# clock1.net
KiCad netlist of a schematic drawn in EAGLE
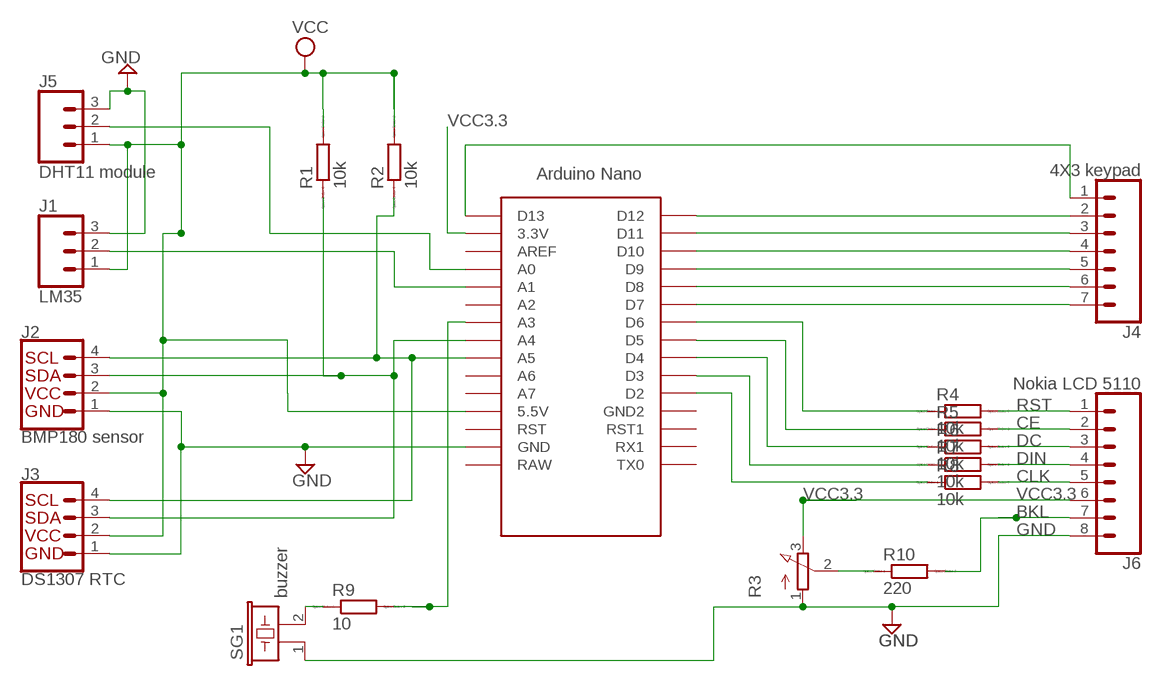
[diagram p0: schematic, sheet 1]

(export (version "E")
  (design (tool "Eeschema 10.0.6"))
  (components
    (comp (ref "J1")
      (value "LM35")
      (footprint "eagle-import:1X03")
      (libsource (lib "eagle-import") (part "CONN_03"))
    )
    (comp (ref "J2")
      (value "BMP180 sensor")
      (footprint "eagle-import:1X04")
      (libsource (lib "eagle-import") (part "I2C_STANDARD"))
    )
    (comp (ref "J3")
      (value "DS1307 RTC")
      (footprint "eagle-import:1X04")
      (libsource (lib "eagle-import") (part "I2C_STANDARD"))
    )
    (comp (ref "J4")
      (value "4X3 keypad")
      (footprint "eagle-import:1X07")
      (libsource (lib "eagle-import") (part "CONN_07"))
    )
    (comp (ref "J5")
      (value "DHT11 module")
      (footprint "eagle-import:1X03")
      (libsource (lib "eagle-import") (part "CONN_03"))
    )
    (comp (ref "J6")
      (value "Nokia LCD 5110")
      (footprint "eagle-import:1X08")
      (libsource (lib "eagle-import") (part "CONN_08{dblquote}"))
    )
    (comp (ref "R1")
      (value "10k")
      (footprint "eagle-import:0204_7")
      (libsource (lib "eagle-import") (part "R0204/7"))
    )
    (comp (ref "R2")
      (value "10k")
      (footprint "eagle-import:0204_7")
      (libsource (lib "eagle-import") (part "R0204/7"))
    )
    (comp (ref "R3")
      (value "3RP/1610N")
      (footprint "eagle-import:3RP_1610N")
      (libsource (lib "eagle-import") (part "3RP/1610N"))
    )
    (comp (ref "R4")
      (value "10k")
      (footprint "eagle-import:0204_7")
      (libsource (lib "eagle-import") (part "R0204/7"))
    )
    (comp (ref "R5")
      (value "10k")
      (footprint "eagle-import:0204_7")
      (libsource (lib "eagle-import") (part "R0204/7"))
    )
    (comp (ref "R6")
      (value "10k")
      (footprint "eagle-import:0204_7")
      (libsource (lib "eagle-import") (part "R0204/7"))
    )
    (comp (ref "R7")
      (value "10k")
      (footprint "eagle-import:0204_7")
      (libsource (lib "eagle-import") (part "R0204/7"))
    )
    (comp (ref "R8")
      (value "10k")
      (footprint "eagle-import:0204_7")
      (libsource (lib "eagle-import") (part "R0204/7"))
    )
    (comp (ref "R9")
      (value "10")
      (footprint "eagle-import:0204_7")
      (libsource (lib "eagle-import") (part "R0204/7"))
    )
    (comp (ref "R10")
      (value "220")
      (footprint "eagle-import:0204_7")
      (libsource (lib "eagle-import") (part "R0204/7"))
    )
    (comp (ref "SG1")
      (value "buzzer")
      (footprint "eagle-import:B_C11L")
      (libsource (lib "eagle-import") (part "B/C11L"))
    )
    (comp (ref "U$1")
      (value "NANO")
      (footprint "eagle-import:NANO")
      (libsource (lib "eagle-import") (part "NANO"))
    )
  )
  (nets
    (net (code "1") (name "/BKL") (class "Default")
      (node (ref "J6") (pin "7") (pinfunction "7_7") (pintype "passive"))
      (node (ref "R10") (pin "2") (pinfunction "2_2") (pintype "passive"))
    )
    (net (code "2") (name "/CE") (class "Default")
      (node (ref "J6") (pin "2") (pinfunction "2_2") (pintype "passive"))
      (node (ref "R5") (pin "2") (pinfunction "2_2") (pintype "passive"))
    )
    (net (code "3") (name "/CLK") (class "Default")
      (node (ref "J6") (pin "5") (pinfunction "5_5") (pintype "passive"))
      (node (ref "R8") (pin "2") (pinfunction "2_2") (pintype "passive"))
    )
    (net (code "4") (name "/DC") (class "Default")
      (node (ref "J6") (pin "3") (pinfunction "3_3") (pintype "passive"))
      (node (ref "R6") (pin "2") (pinfunction "2_2") (pintype "passive"))
    )
    (net (code "5") (name "/DIN") (class "Default")
      (node (ref "J6") (pin "4") (pinfunction "4_4") (pintype "passive"))
      (node (ref "R7") (pin "2") (pinfunction "2_2") (pintype "passive"))
    )
    (net (code "6") (name "/RST") (class "Default")
      (node (ref "J6") (pin "1") (pinfunction "1_1") (pintype "passive"))
      (node (ref "R4") (pin "2") (pinfunction "2_2") (pintype "passive"))
    )
    (net (code "7") (name "/VCC3.3") (class "Default")
      (node (ref "J6") (pin "6") (pinfunction "6_6") (pintype "passive"))
      (node (ref "R3") (pin "3") (pinfunction "E_3") (pintype "passive"))
      (node (ref "U$1") (pin "3.3V") (pinfunction "3.3V_3.3V") (pintype "bidirectional"))
    )
    (net (code "8") (name "GND") (class "Default")
      (node (ref "J1") (pin "3") (pinfunction "3_3") (pintype "passive"))
      (node (ref "J2") (pin "1") (pinfunction "1_1") (pintype "power_in"))
      (node (ref "J3") (pin "1") (pinfunction "1_1") (pintype "power_in"))
      (node (ref "J5") (pin "3") (pinfunction "3_3") (pintype "passive"))
      (node (ref "J6") (pin "8") (pinfunction "8_8") (pintype "passive"))
      (node (ref "R3") (pin "1") (pinfunction "A_1") (pintype "passive"))
      (node (ref "SG1") (pin "1") (pinfunction "1_1") (pintype "passive"))
      (node (ref "U$1") (pin "GND") (pinfunction "GND_GND") (pintype "bidirectional"))
    )
    (net (code "9") (name "Net-(J1-Pad2)") (class "Default")
      (node (ref "J1") (pin "2") (pinfunction "2_2") (pintype "passive"))
      (node (ref "U$1") (pin "A1") (pinfunction "A1_A1") (pintype "bidirectional"))
    )
    (net (code "10") (name "Net-(J2-Pad3)") (class "Default")
      (node (ref "J2") (pin "3") (pinfunction "3_3") (pintype "passive"))
      (node (ref "J3") (pin "3") (pinfunction "3_3") (pintype "passive"))
      (node (ref "R1") (pin "1") (pinfunction "1_1") (pintype "passive"))
      (node (ref "U$1") (pin "A4") (pinfunction "A4_A4") (pintype "bidirectional"))
    )
    (net (code "11") (name "Net-(J2-Pad4)") (class "Default")
      (node (ref "J2") (pin "4") (pinfunction "4_4") (pintype "passive"))
      (node (ref "J3") (pin "4") (pinfunction "4_4") (pintype "passive"))
      (node (ref "R2") (pin "1") (pinfunction "1_1") (pintype "passive"))
      (node (ref "U$1") (pin "A5") (pinfunction "A5_A5") (pintype "bidirectional"))
    )
    (net (code "12") (name "Net-(J4-Pad1)") (class "Default")
      (node (ref "J4") (pin "1") (pinfunction "1_1") (pintype "passive"))
      (node (ref "U$1") (pin "D13") (pinfunction "D13_D13") (pintype "bidirectional"))
    )
    (net (code "13") (name "Net-(J4-Pad2)") (class "Default")
      (node (ref "J4") (pin "2") (pinfunction "2_2") (pintype "passive"))
      (node (ref "U$1") (pin "D12") (pinfunction "D12_D12") (pintype "bidirectional"))
    )
    (net (code "14") (name "Net-(J4-Pad3)") (class "Default")
      (node (ref "J4") (pin "3") (pinfunction "3_3") (pintype "passive"))
      (node (ref "U$1") (pin "D11") (pinfunction "D11_D11") (pintype "bidirectional"))
    )
    (net (code "15") (name "Net-(J4-Pad4)") (class "Default")
      (node (ref "J4") (pin "4") (pinfunction "4_4") (pintype "passive"))
      (node (ref "U$1") (pin "D10") (pinfunction "D10_D10") (pintype "bidirectional"))
    )
    (net (code "16") (name "Net-(J4-Pad5)") (class "Default")
      (node (ref "J4") (pin "5") (pinfunction "5_5") (pintype "passive"))
      (node (ref "U$1") (pin "D9") (pinfunction "D9_D9") (pintype "bidirectional"))
    )
    (net (code "17") (name "Net-(J4-Pad6)") (class "Default")
      (node (ref "J4") (pin "6") (pinfunction "6_6") (pintype "passive"))
      (node (ref "U$1") (pin "D8") (pinfunction "D8_D8") (pintype "bidirectional"))
    )
    (net (code "18") (name "Net-(J4-Pad7)") (class "Default")
      (node (ref "J4") (pin "7") (pinfunction "7_7") (pintype "passive"))
      (node (ref "U$1") (pin "D7") (pinfunction "D7_D7") (pintype "bidirectional"))
    )
    (net (code "19") (name "Net-(J5-Pad2)") (class "Default")
      (node (ref "J5") (pin "2") (pinfunction "2_2") (pintype "passive"))
      (node (ref "U$1") (pin "A0") (pinfunction "A0_A0") (pintype "bidirectional"))
    )
    (net (code "20") (name "Net-(R3-S)") (class "Default")
      (node (ref "R10") (pin "1") (pinfunction "1_1") (pintype "passive"))
      (node (ref "R3") (pin "2") (pinfunction "S_2") (pintype "passive"))
    )
    (net (code "21") (name "Net-(R4-Pad1)") (class "Default")
      (node (ref "R4") (pin "1") (pinfunction "1_1") (pintype "passive"))
      (node (ref "U$1") (pin "D6") (pinfunction "D6_D6") (pintype "bidirectional"))
    )
    (net (code "22") (name "Net-(R5-Pad1)") (class "Default")
      (node (ref "R5") (pin "1") (pinfunction "1_1") (pintype "passive"))
      (node (ref "U$1") (pin "D5") (pinfunction "D5_D5") (pintype "bidirectional"))
    )
    (net (code "23") (name "Net-(R6-Pad1)") (class "Default")
      (node (ref "R6") (pin "1") (pinfunction "1_1") (pintype "passive"))
      (node (ref "U$1") (pin "D4") (pinfunction "D4_D4") (pintype "bidirectional"))
    )
    (net (code "24") (name "Net-(R7-Pad1)") (class "Default")
      (node (ref "R7") (pin "1") (pinfunction "1_1") (pintype "passive"))
      (node (ref "U$1") (pin "D3") (pinfunction "D3_D3") (pintype "bidirectional"))
    )
    (net (code "25") (name "Net-(R8-Pad1)") (class "Default")
      (node (ref "R8") (pin "1") (pinfunction "1_1") (pintype "passive"))
      (node (ref "U$1") (pin "D2") (pinfunction "D2_D2") (pintype "bidirectional"))
    )
    (net (code "26") (name "Net-(R9-Pad1)") (class "Default")
      (node (ref "R9") (pin "1") (pinfunction "1_1") (pintype "passive"))
      (node (ref "SG1") (pin "2") (pinfunction "2_2") (pintype "passive"))
    )
    (net (code "27") (name "Net-(R9-Pad2)") (class "Default")
      (node (ref "R9") (pin "2") (pinfunction "2_2") (pintype "passive"))
      (node (ref "U$1") (pin "A3") (pinfunction "A3_A3") (pintype "bidirectional"))
    )
    (net (code "28") (name "VCC") (class "Default")
      (node (ref "J1") (pin "1") (pinfunction "1_1") (pintype "passive"))
      (node (ref "J2") (pin "2") (pinfunction "2_2") (pintype "power_in"))
      (node (ref "J3") (pin "2") (pinfunction "2_2") (pintype "power_in"))
      (node (ref "J5") (pin "1") (pinfunction "1_1") (pintype "passive"))
      (node (ref "R1") (pin "2") (pinfunction "2_2") (pintype "passive"))
      (node (ref "R2") (pin "2") (pinfunction "2_2") (pintype "passive"))
      (node (ref "U$1") (pin "5V") (pinfunction "5.5V_5V") (pintype "bidirectional"))
    )
    (net (code "29") (name "unconnected-(U$1-GND2-PadGND1)") (class "Default")
      (node (ref "U$1") (pin "GND1") (pinfunction "GND2_GND1") (pintype "bidirectional"))
    )
    (net (code "30") (name "unconnected-(U$1-PadA2)") (class "Default")
      (node (ref "U$1") (pin "A2") (pinfunction "A2_A2") (pintype "bidirectional"))
    )
    (net (code "31") (name "unconnected-(U$1-PadA6)") (class "Default")
      (node (ref "U$1") (pin "A6") (pinfunction "A6_A6") (pintype "bidirectional"))
    )
    (net (code "32") (name "unconnected-(U$1-PadA7)") (class "Default")
      (node (ref "U$1") (pin "A7") (pinfunction "A7_A7") (pintype "bidirectional"))
    )
    (net (code "33") (name "unconnected-(U$1-PadAREF)") (class "Default")
      (node (ref "U$1") (pin "AREF") (pinfunction "AREF_AREF") (pintype "bidirectional"))
    )
    (net (code "34") (name "unconnected-(U$1-PadICSP1)") (class "Default")
      (node (ref "U$1") (pin "ICSP1") (pinfunction "ICSP1_ICSP1") (pintype "bidirectional"))
    )
    (net (code "35") (name "unconnected-(U$1-PadICSP2)") (class "Default")
      (node (ref "U$1") (pin "ICSP2") (pinfunction "ICSP2_ICSP2") (pintype "bidirectional"))
    )
    (net (code "36") (name "unconnected-(U$1-PadICSP3)") (class "Default")
      (node (ref "U$1") (pin "ICSP3") (pinfunction "ICSP3_ICSP3") (pintype "bidirectional"))
    )
    (net (code "37") (name "unconnected-(U$1-PadICSP4)") (class "Default")
      (node (ref "U$1") (pin "ICSP4") (pinfunction "ICSP4_ICSP4") (pintype "bidirectional"))
    )
    (net (code "38") (name "unconnected-(U$1-PadICSP5)") (class "Default")
      (node (ref "U$1") (pin "ICSP5") (pinfunction "ICSP5_ICSP5") (pintype "bidirectional"))
    )
    (net (code "39") (name "unconnected-(U$1-PadICSP6)") (class "Default")
      (node (ref "U$1") (pin "ICSP6") (pinfunction "ICSP6_ICSP6") (pintype "bidirectional"))
    )
    (net (code "40") (name "unconnected-(U$1-PadRAW)") (class "Default")
      (node (ref "U$1") (pin "RAW") (pinfunction "RAW_RAW") (pintype "bidirectional"))
    )
    (net (code "41") (name "unconnected-(U$1-PadRST)") (class "Default")
      (node (ref "U$1") (pin "RST") (pinfunction "RST_RST") (pintype "bidirectional"))
    )
    (net (code "42") (name "unconnected-(U$1-PadRST1)") (class "Default")
      (node (ref "U$1") (pin "RST1") (pinfunction "RST1_RST1") (pintype "bidirectional"))
    )
    (net (code "43") (name "unconnected-(U$1-PadRX1)") (class "Default")
      (node (ref "U$1") (pin "RX1") (pinfunction "RX1_RX1") (pintype "bidirectional"))
    )
    (net (code "44") (name "unconnected-(U$1-PadTX0)") (class "Default")
      (node (ref "U$1") (pin "TX0") (pinfunction "TX0_TX0") (pintype "bidirectional"))
    )
  )
)
